# ADC.net
KiCad netlist of a schematic drawn in Altium Designer
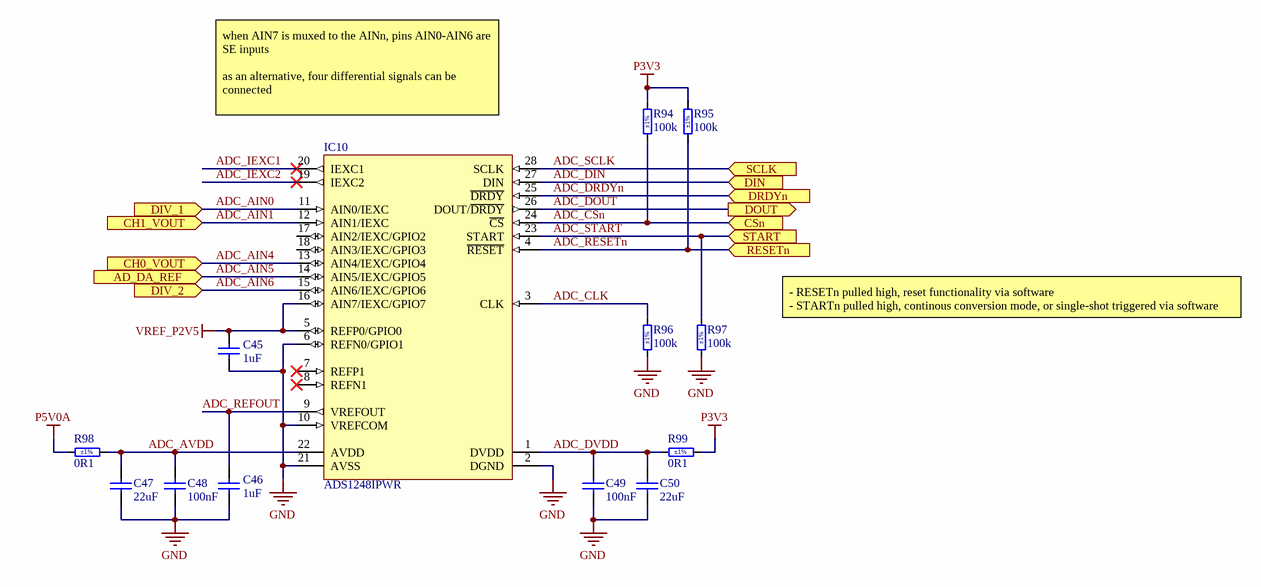
[diagram p0: ADC.SchDoc]

(export (version "E")
  (design (tool "Eeschema 10.0.6"))
  (components
    (comp (ref "C45")
      (value "1uF")
      (footprint "CAPC1005X55N")
      (description "Non-polarised capacitor")
      (fields
        (field (name "PART NUMBER") "CC0402_1UF_16V_10%_X5R")
        (field (name "VOLTAGE") "16V")
        (field (name "AUTHOR") "CERN DEM JLC")
      )
      (libsource (lib "Capacitors") (part "Capacitor - non polarized"))
    )
    (comp (ref "C46")
      (value "1uF")
      (footprint "CAPC1005X55N")
      (description "Non-polarised capacitor")
      (fields
        (field (name "PART NUMBER") "CC0402_1UF_16V_10%_X5R")
        (field (name "VOLTAGE") "16V")
        (field (name "AUTHOR") "CERN DEM JLC")
      )
      (libsource (lib "Capacitors") (part "Capacitor - non polarized"))
    )
    (comp (ref "C47")
      (value "22uF")
      (footprint "CAPC3216X180N")
      (description "Non-polarised capacitor")
      (fields
        (field (name "PART NUMBER") "CC1206_22UF_25V_20%_X5R")
        (field (name "VOLTAGE") "25V")
        (field (name "AUTHOR") "CERN DEM WB")
      )
      (libsource (lib "Capacitors") (part "Capacitor - non polarized"))
    )
    (comp (ref "C48")
      (value "100nF")
      (footprint "CAPC1005X55N")
      (description "Non-polarised capacitor")
      (fields
        (field (name "PART NUMBER") "CC0402_100NF_50V_10%_X7R")
        (field (name "VOLTAGE") "50V")
        (field (name "AUTHOR") "CERN DEM MR")
      )
      (libsource (lib "Capacitors") (part "Capacitor - non polarized"))
    )
    (comp (ref "C49")
      (value "100nF")
      (footprint "CAPC1005X55N")
      (description "Non-polarised capacitor")
      (fields
        (field (name "PART NUMBER") "CC0402_100NF_50V_10%_X7R")
        (field (name "VOLTAGE") "50V")
        (field (name "AUTHOR") "CERN DEM MR")
      )
      (libsource (lib "Capacitors") (part "Capacitor - non polarized"))
    )
    (comp (ref "C50")
      (value "22uF")
      (footprint "CAPC3216X180N")
      (description "Non-polarised capacitor")
      (fields
        (field (name "PART NUMBER") "CC1206_22UF_25V_20%_X5R")
        (field (name "VOLTAGE") "25V")
        (field (name "AUTHOR") "CERN DEM WB")
      )
      (libsource (lib "Capacitors") (part "Capacitor - non polarized"))
    )
    (comp (ref "IC10")
      (value "ADS1248IPWR")
      (footprint "SOP65P640X120-28N")
      (description "24-Bit Analog-to-Digital Converter for Temperature Sensors")
      (fields (field (name "MANUFACTURER") "TEXAS INSTRUMENTS") (field (name "AUTHOR") "CERN DEM JLC"))
      (libsource (lib "ICs And Semiconductors") (part "ADS1248"))
    )
    (comp (ref "R94")
      (value "100k")
      (footprint "RESC1005X40N")
      (description "Resistor - 1%")
      (fields
        (field (name "TOLERANCE") "±1%")
        (field (name "PART NUMBER") "R0402_100K_1%_0.0625W_100PPM")
        (field (name "POWER") "0.0625W")
        (field (name "AUTHOR") "CERN DEM JLC")
      )
      (libsource (lib "Resistors") (part "Resistor - 1%"))
    )
    (comp (ref "R95")
      (value "100k")
      (footprint "RESC1005X40N")
      (description "Resistor - 1%")
      (fields
        (field (name "TOLERANCE") "±1%")
        (field (name "PART NUMBER") "R0402_100K_1%_0.0625W_100PPM")
        (field (name "POWER") "0.0625W")
        (field (name "AUTHOR") "CERN DEM JLC")
      )
      (libsource (lib "Resistors") (part "Resistor - 1%"))
    )
    (comp (ref "R96")
      (value "100k")
      (footprint "RESC1005X40N")
      (description "Resistor - 1%")
      (fields
        (field (name "TOLERANCE") "±1%")
        (field (name "PART NUMBER") "R0402_100K_1%_0.0625W_100PPM")
        (field (name "POWER") "0.0625W")
        (field (name "AUTHOR") "CERN DEM JLC")
      )
      (libsource (lib "Resistors") (part "Resistor - 1%"))
    )
    (comp (ref "R97")
      (value "100k")
      (footprint "RESC1005X40N")
      (description "Resistor - 1%")
      (fields
        (field (name "TOLERANCE") "±1%")
        (field (name "PART NUMBER") "R0402_100K_1%_0.0625W_100PPM")
        (field (name "POWER") "0.0625W")
        (field (name "AUTHOR") "CERN DEM JLC")
      )
      (libsource (lib "Resistors") (part "Resistor - 1%"))
    )
    (comp (ref "R98")
      (value "0R1")
      (footprint "RESC1608X55N")
      (description "Resistor - 1%")
      (fields
        (field (name "TOLERANCE") "±1%")
        (field (name "PART NUMBER") "R0603_0R1_1%_0.1W_200PPM")
        (field (name "POWER") "0.1W")
        (field (name "AUTHOR") "CERN DEM JMW")
      )
      (libsource (lib "Resistors") (part "Resistor - 1%"))
    )
    (comp (ref "R99")
      (value "0R1")
      (footprint "RESC1608X55N")
      (description "Resistor - 1%")
      (fields
        (field (name "TOLERANCE") "±1%")
        (field (name "PART NUMBER") "R0603_0R1_1%_0.1W_200PPM")
        (field (name "POWER") "0.1W")
        (field (name "AUTHOR") "CERN DEM JMW")
      )
      (libsource (lib "Resistors") (part "Resistor - 1%"))
    )
  )
  (nets
    (net (code "1") (name "/ADC_AIN0") (class "Default")
      (node (ref "IC10") (pin "11") (pinfunction "AIN0/IEXC_11") (pintype "input"))
    )
    (net (code "2") (name "/ADC_AIN1") (class "Default")
      (node (ref "IC10") (pin "12") (pinfunction "AIN1/IEXC_12") (pintype "input"))
    )
    (net (code "3") (name "/ADC_AIN4") (class "Default")
      (node (ref "IC10") (pin "13") (pinfunction "AIN4/IEXC/GPIO4_13") (pintype "bidirectional"))
    )
    (net (code "4") (name "/ADC_AIN5") (class "Default")
      (node (ref "IC10") (pin "14") (pinfunction "AIN5/IEXC/GPIO5_14") (pintype "bidirectional"))
    )
    (net (code "5") (name "/ADC_AIN6") (class "Default")
      (node (ref "IC10") (pin "15") (pinfunction "AIN6/IEXC/GPIO6_15") (pintype "bidirectional"))
    )
    (net (code "6") (name "/ADC_AVDD") (class "Default")
      (node (ref "C47") (pin "2") (pinfunction "2_2") (pintype "passive"))
      (node (ref "C48") (pin "2") (pinfunction "2_2") (pintype "passive"))
      (node (ref "IC10") (pin "22") (pinfunction "AVDD_22") (pintype "power_in"))
      (node (ref "R98") (pin "1") (pinfunction "1_1") (pintype "passive"))
    )
    (net (code "7") (name "/ADC_CLK") (class "Default")
      (node (ref "IC10") (pin "3") (pinfunction "CLK_3") (pintype "input"))
      (node (ref "R96") (pin "2") (pinfunction "2_2") (pintype "passive"))
    )
    (net (code "8") (name "/ADC_CSn") (class "Default")
      (node (ref "IC10") (pin "24") (pinfunction "~{CS}_24") (pintype "input"))
      (node (ref "R94") (pin "1") (pinfunction "1_1") (pintype "passive"))
    )
    (net (code "9") (name "/ADC_DIN") (class "Default")
      (node (ref "IC10") (pin "27") (pinfunction "DIN_27") (pintype "input"))
    )
    (net (code "10") (name "/ADC_DOUT") (class "Default")
      (node (ref "IC10") (pin "26") (pinfunction "DOUT/~{DRDY}_26") (pintype "output"))
    )
    (net (code "11") (name "/ADC_DRDYn") (class "Default")
      (node (ref "IC10") (pin "25") (pinfunction "~{DRDY}_25") (pintype "input"))
    )
    (net (code "12") (name "/ADC_DVDD") (class "Default")
      (node (ref "C49") (pin "2") (pinfunction "2_2") (pintype "passive"))
      (node (ref "C50") (pin "2") (pinfunction "2_2") (pintype "passive"))
      (node (ref "IC10") (pin "1") (pinfunction "DVDD_1") (pintype "power_in"))
      (node (ref "R99") (pin "2") (pinfunction "2_2") (pintype "passive"))
    )
    (net (code "13") (name "/ADC_IEXC1") (class "Default")
      (node (ref "IC10") (pin "20") (pinfunction "IEXC1_20") (pintype "output+no_connect"))
    )
    (net (code "14") (name "/ADC_IEXC2") (class "Default")
      (node (ref "IC10") (pin "19") (pinfunction "IEXC2_19") (pintype "output+no_connect"))
    )
    (net (code "15") (name "/ADC_REFOUT") (class "Default")
      (node (ref "C46") (pin "2") (pinfunction "2_2") (pintype "passive"))
      (node (ref "IC10") (pin "9") (pinfunction "VREFOUT_9") (pintype "output"))
    )
    (net (code "16") (name "/ADC_RESETn") (class "Default")
      (node (ref "IC10") (pin "4") (pinfunction "~{RESET}_4") (pintype "input"))
      (node (ref "R95") (pin "1") (pinfunction "1_1") (pintype "passive"))
    )
    (net (code "17") (name "/ADC_SCLK") (class "Default")
      (node (ref "IC10") (pin "28") (pinfunction "SCLK_28") (pintype "input"))
    )
    (net (code "18") (name "/ADC_START") (class "Default")
      (node (ref "IC10") (pin "23") (pinfunction "START_23") (pintype "input"))
      (node (ref "R97") (pin "2") (pinfunction "2_2") (pintype "passive"))
    )
    (net (code "19") (name "GND") (class "Default")
      (node (ref "C45") (pin "1") (pinfunction "1_1") (pintype "passive"))
      (node (ref "C46") (pin "1") (pinfunction "1_1") (pintype "passive"))
      (node (ref "C47") (pin "1") (pinfunction "1_1") (pintype "passive"))
      (node (ref "C48") (pin "1") (pinfunction "1_1") (pintype "passive"))
      (node (ref "C49") (pin "1") (pinfunction "1_1") (pintype "passive"))
      (node (ref "C50") (pin "1") (pinfunction "1_1") (pintype "passive"))
      (node (ref "IC10") (pin "10") (pinfunction "VREFCOM_10") (pintype "input"))
      (node (ref "IC10") (pin "2") (pinfunction "DGND_2") (pintype "power_in"))
      (node (ref "IC10") (pin "21") (pinfunction "AVSS_21") (pintype "power_in"))
      (node (ref "IC10") (pin "6") (pinfunction "REFN0/GPIO1_6") (pintype "bidirectional"))
      (node (ref "R96") (pin "1") (pinfunction "1_1") (pintype "passive"))
      (node (ref "R97") (pin "1") (pinfunction "1_1") (pintype "passive"))
    )
    (net (code "20") (name "P3V3") (class "Default")
      (node (ref "R94") (pin "2") (pinfunction "2_2") (pintype "passive"))
      (node (ref "R95") (pin "2") (pinfunction "2_2") (pintype "passive"))
      (node (ref "R99") (pin "1") (pinfunction "1_1") (pintype "passive"))
    )
    (net (code "21") (name "P5V0A") (class "Default")
      (node (ref "R98") (pin "2") (pinfunction "2_2") (pintype "passive"))
    )
    (net (code "22") (name "VREF_P2V5") (class "Default")
      (node (ref "C45") (pin "2") (pinfunction "2_2") (pintype "passive"))
      (node (ref "IC10") (pin "16") (pinfunction "AIN7/IEXC/GPIO7_16") (pintype "bidirectional"))
      (node (ref "IC10") (pin "5") (pinfunction "REFP0/GPIO0_5") (pintype "bidirectional"))
    )
    (net (code "23") (name "unconnected-(IC10-AIN2{slash}IEXC{slash}GPIO2-Pad17)") (class "Default")
      (node (ref "IC10") (pin "17") (pinfunction "AIN2/IEXC/GPIO2_17") (pintype "bidirectional"))
    )
    (net (code "24") (name "unconnected-(IC10-AIN3{slash}IEXC{slash}GPIO3-Pad18)") (class "Default")
      (node (ref "IC10") (pin "18") (pinfunction "AIN3/IEXC/GPIO3_18") (pintype "bidirectional"))
    )
    (net (code "25") (name "unconnected-(IC10-REFN1-Pad8)") (class "Default")
      (node (ref "IC10") (pin "8") (pinfunction "REFN1_8") (pintype "input+no_connect"))
    )
    (net (code "26") (name "unconnected-(IC10-REFP1-Pad7)") (class "Default")
      (node (ref "IC10") (pin "7") (pinfunction "REFP1_7") (pintype "input+no_connect"))
    )
  )
)
